# WL-Power.net
KiCad netlist of a schematic drawn in Altium Designer
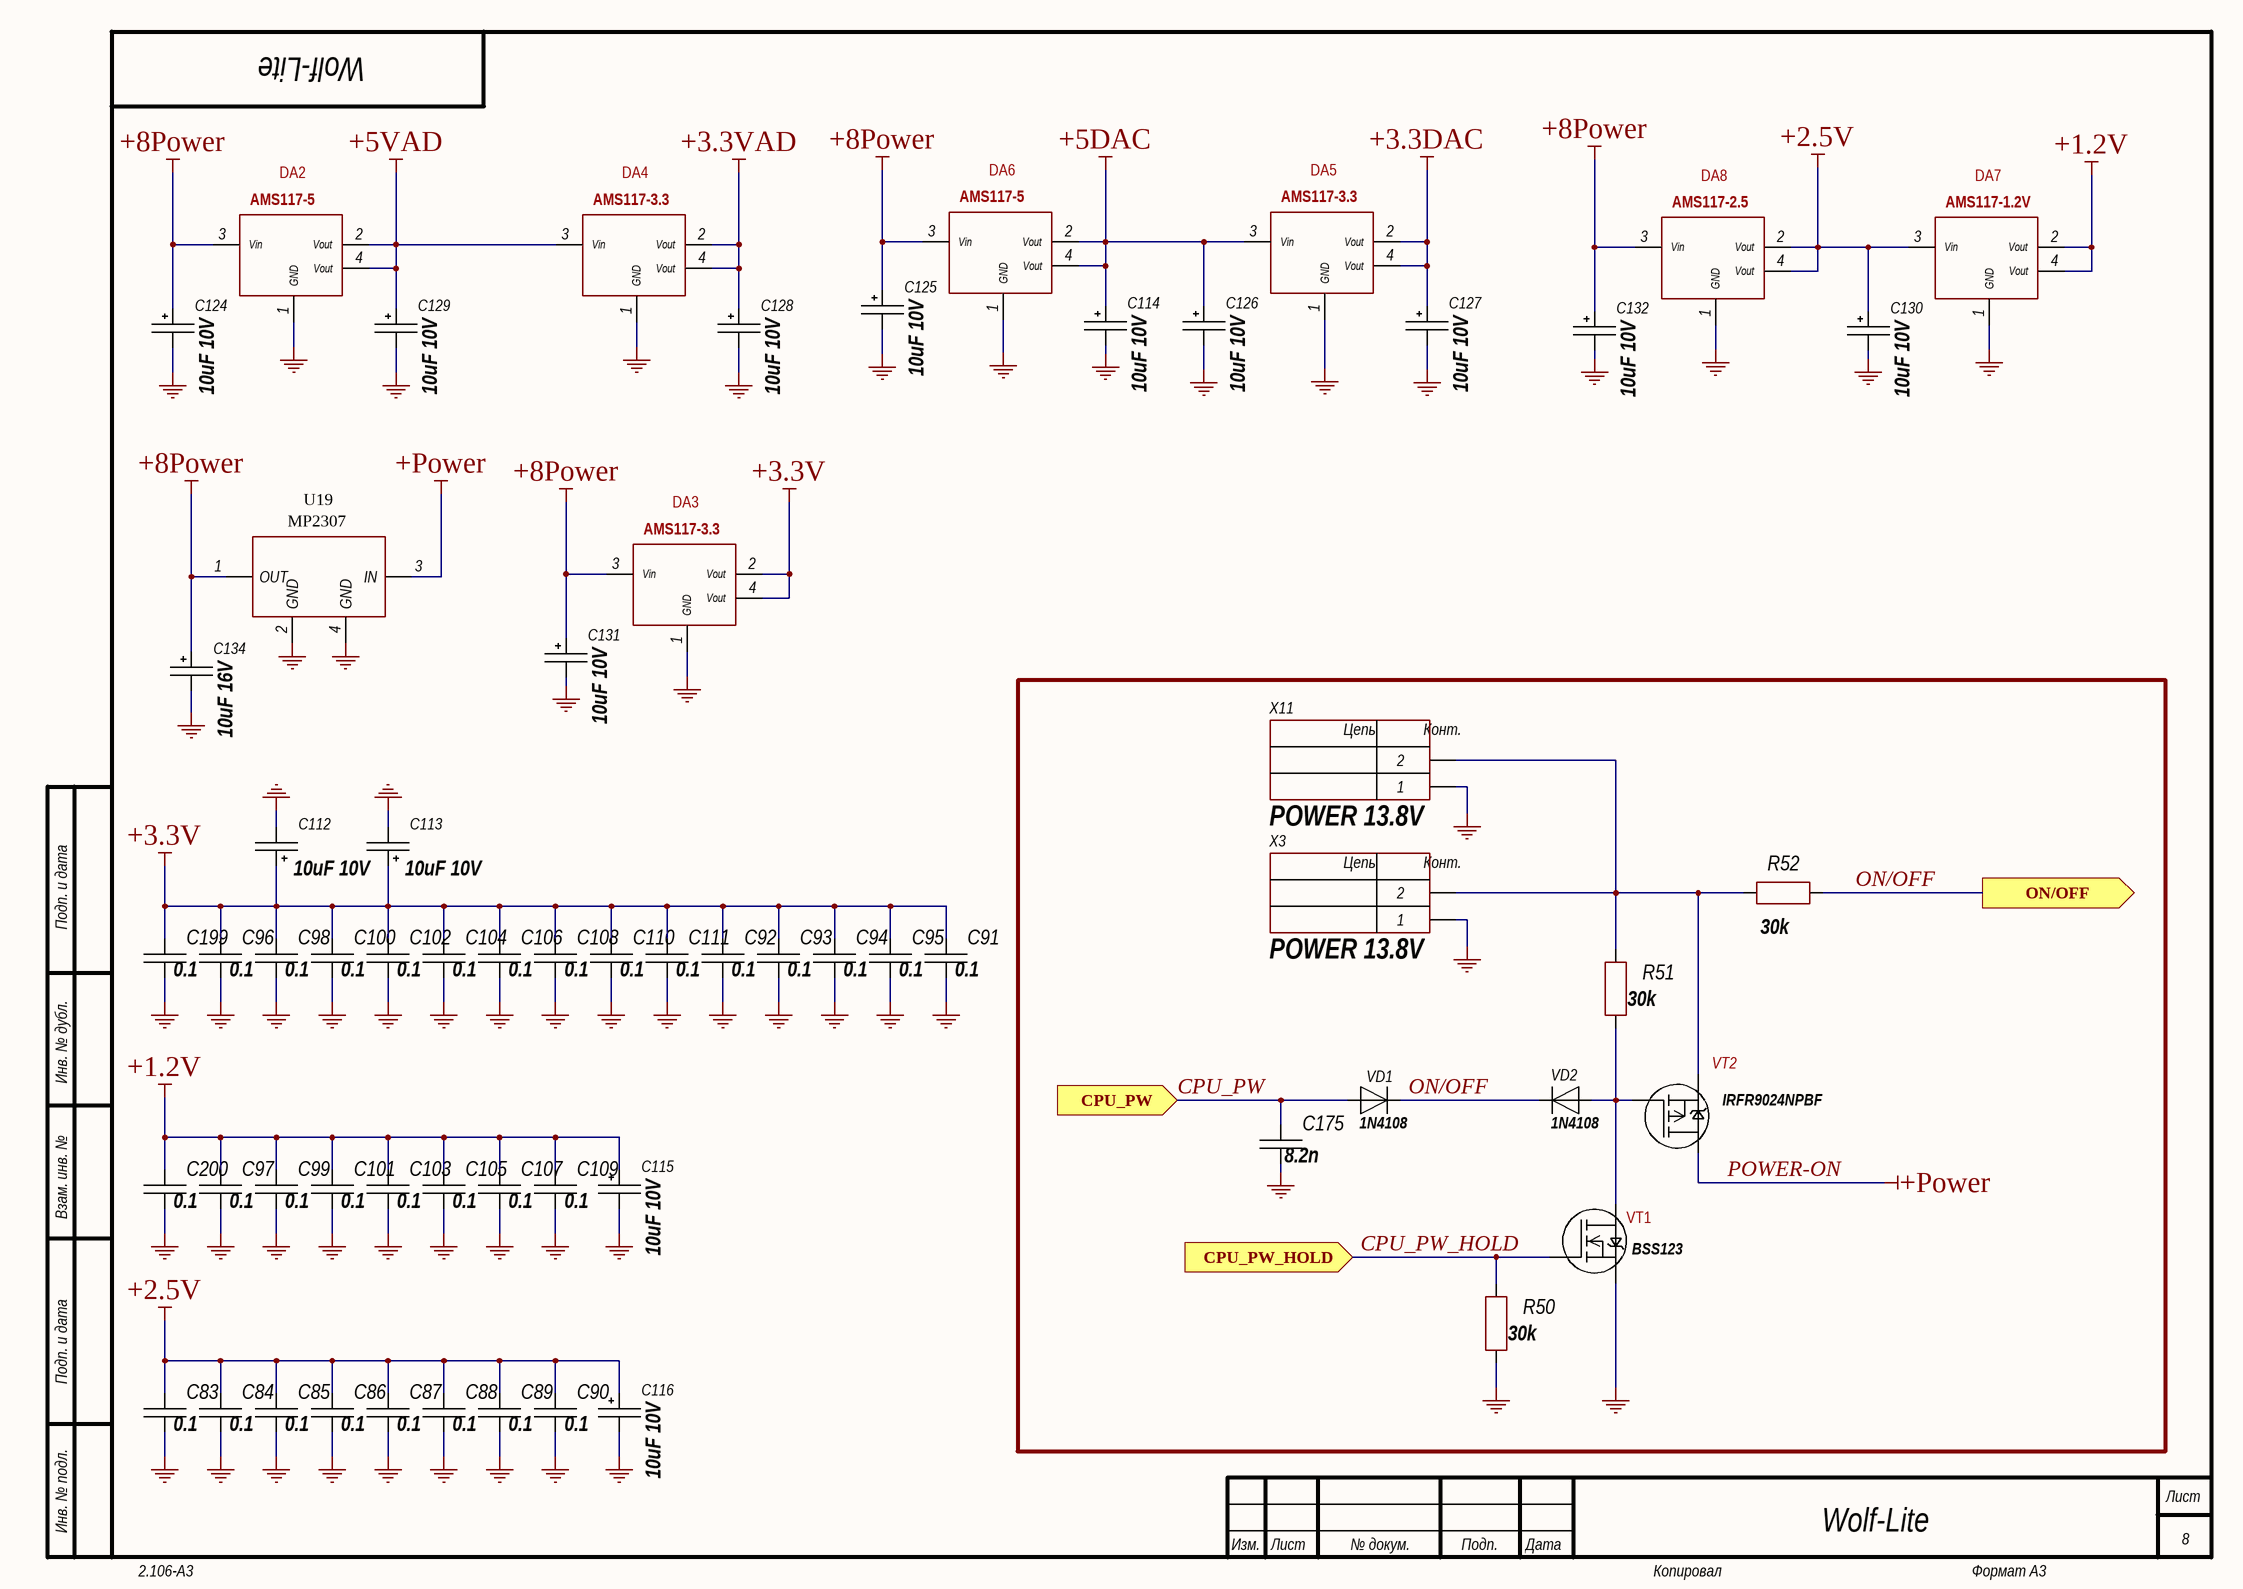
[diagram p0: WL-Power.SchDoc]

(export (version "E")
  (design (tool "Eeschema 10.0.6"))
  (components
    (comp (ref "C83")
      (value "0.1")
      (footprint "standard:CH0805C")
      (libsource (lib "Discrete") (part "Capacitor"))
    )
    (comp (ref "C84")
      (value "0.1")
      (footprint "standard:CH0805C")
      (libsource (lib "Discrete") (part "Capacitor"))
    )
    (comp (ref "C85")
      (value "0.1")
      (footprint "standard:CH0805C")
      (libsource (lib "Discrete") (part "Capacitor"))
    )
    (comp (ref "C86")
      (value "0.1")
      (footprint "standard:CH0805C")
      (libsource (lib "Discrete") (part "Capacitor"))
    )
    (comp (ref "C87")
      (value "0.1")
      (footprint "standard:CH0805C")
      (libsource (lib "Discrete") (part "Capacitor"))
    )
    (comp (ref "C88")
      (value "0.1")
      (footprint "standard:CH0805C")
      (libsource (lib "Discrete") (part "Capacitor"))
    )
    (comp (ref "C89")
      (value "0.1")
      (footprint "standard:CH0805C")
      (libsource (lib "Discrete") (part "Capacitor"))
    )
    (comp (ref "C90")
      (value "0.1")
      (footprint "standard:CH0805C")
      (libsource (lib "Discrete") (part "Capacitor"))
    )
    (comp (ref "C91")
      (value "0.1")
      (footprint "standard:CH0805C")
      (libsource (lib "Discrete") (part "Capacitor"))
    )
    (comp (ref "C92")
      (value "0.1")
      (footprint "standard:CH0805C")
      (libsource (lib "Discrete") (part "Capacitor"))
    )
    (comp (ref "C93")
      (value "0.1")
      (footprint "standard:CH0805C")
      (libsource (lib "Discrete") (part "Capacitor"))
    )
    (comp (ref "C94")
      (value "0.1")
      (footprint "standard:CH0805C")
      (libsource (lib "Discrete") (part "Capacitor"))
    )
    (comp (ref "C95")
      (value "0.1")
      (footprint "standard:CH0805C")
      (libsource (lib "Discrete") (part "Capacitor"))
    )
    (comp (ref "C96")
      (value "0.1")
      (footprint "standard:CH0805C")
      (libsource (lib "Discrete") (part "Capacitor"))
    )
    (comp (ref "C97")
      (value "0.1")
      (footprint "standard:CH0805C")
      (libsource (lib "Discrete") (part "Capacitor"))
    )
    (comp (ref "C98")
      (value "0.1")
      (footprint "standard:CH0805C")
      (libsource (lib "Discrete") (part "Capacitor"))
    )
    (comp (ref "C99")
      (value "0.1")
      (footprint "standard:CH0805C")
      (libsource (lib "Discrete") (part "Capacitor"))
    )
    (comp (ref "C100")
      (value "0.1")
      (footprint "standard:CH0805C")
      (libsource (lib "Discrete") (part "Capacitor"))
    )
    (comp (ref "C101")
      (value "0.1")
      (footprint "standard:CH0805C")
      (libsource (lib "Discrete") (part "Capacitor"))
    )
    (comp (ref "C102")
      (value "0.1")
      (footprint "standard:CH0805C")
      (libsource (lib "Discrete") (part "Capacitor"))
    )
    (comp (ref "C103")
      (value "0.1")
      (footprint "standard:CH0805C")
      (libsource (lib "Discrete") (part "Capacitor"))
    )
    (comp (ref "C104")
      (value "0.1")
      (footprint "standard:CH0805C")
      (libsource (lib "Discrete") (part "Capacitor"))
    )
    (comp (ref "C105")
      (value "0.1")
      (footprint "standard:CH0805C")
      (libsource (lib "Discrete") (part "Capacitor"))
    )
    (comp (ref "C106")
      (value "0.1")
      (footprint "standard:CH0805C")
      (libsource (lib "Discrete") (part "Capacitor"))
    )
    (comp (ref "C107")
      (value "0.1")
      (footprint "standard:CH0805C")
      (libsource (lib "Discrete") (part "Capacitor"))
    )
    (comp (ref "C108")
      (value "0.1")
      (footprint "standard:CH0805C")
      (libsource (lib "Discrete") (part "Capacitor"))
    )
    (comp (ref "C109")
      (value "0.1")
      (footprint "standard:CH0805C")
      (libsource (lib "Discrete") (part "Capacitor"))
    )
    (comp (ref "C110")
      (value "0.1")
      (footprint "standard:CH0805C")
      (libsource (lib "Discrete") (part "Capacitor"))
    )
    (comp (ref "C111")
      (value "0.1")
      (footprint "standard:CH0805C")
      (libsource (lib "Discrete") (part "Capacitor"))
    )
    (comp (ref "C112")
      (value "10uF 10V")
      (footprint "standard:TANTAL_B")
      (libsource (lib "Discrete") (part "TantalCap"))
    )
    (comp (ref "C113")
      (value "10uF 10V")
      (footprint "standard:TANTAL_B")
      (libsource (lib "Discrete") (part "TantalCap"))
    )
    (comp (ref "C114")
      (value "10uF 10V")
      (footprint "standard:TANTAL_B")
      (libsource (lib "Discrete") (part "TantalCap"))
    )
    (comp (ref "C115")
      (value "10uF 10V")
      (footprint "standard:TANTAL_B")
      (libsource (lib "Discrete") (part "TantalCap"))
    )
    (comp (ref "C116")
      (value "10uF 10V")
      (footprint "standard:TANTAL_B")
      (libsource (lib "Discrete") (part "TantalCap"))
    )
    (comp (ref "C124")
      (value "10uF 10V")
      (footprint "standard:TANTAL_B")
      (libsource (lib "Discrete") (part "TantalCap"))
    )
    (comp (ref "C125")
      (value "10uF 10V")
      (footprint "standard:TANTAL_B")
      (libsource (lib "Discrete") (part "TantalCap"))
    )
    (comp (ref "C126")
      (value "10uF 10V")
      (footprint "standard:TANTAL_B")
      (libsource (lib "Discrete") (part "TantalCap"))
    )
    (comp (ref "C127")
      (value "10uF 10V")
      (footprint "standard:TANTAL_B")
      (libsource (lib "Discrete") (part "TantalCap"))
    )
    (comp (ref "C128")
      (value "10uF 10V")
      (footprint "standard:TANTAL_B")
      (libsource (lib "Discrete") (part "TantalCap"))
    )
    (comp (ref "C129")
      (value "10uF 10V")
      (footprint "standard:TANTAL_B")
      (libsource (lib "Discrete") (part "TantalCap"))
    )
    (comp (ref "C130")
      (value "10uF 10V")
      (footprint "standard:TANTAL_B")
      (libsource (lib "Discrete") (part "TantalCap"))
    )
    (comp (ref "C131")
      (value "10uF 10V")
      (footprint "standard:TANTAL_B")
      (libsource (lib "Discrete") (part "TantalCap"))
    )
    (comp (ref "C132")
      (value "10uF 10V")
      (footprint "standard:TANTAL_B")
      (libsource (lib "Discrete") (part "TantalCap"))
    )
    (comp (ref "C134")
      (value "10uF 16V")
      (footprint "POLIMER-D")
      (libsource (lib "Discrete") (part "TantalCap"))
    )
    (comp (ref "C175")
      (value "8.2n")
      (footprint "standard:CH0805C")
      (libsource (lib "Discrete") (part "Capacitor"))
    )
    (comp (ref "C199")
      (value "0.1")
      (footprint "standard:CH0805C")
      (libsource (lib "Discrete") (part "Capacitor"))
    )
    (comp (ref "C200")
      (value "0.1")
      (footprint "standard:CH0805C")
      (libsource (lib "Discrete") (part "Capacitor"))
    )
    (comp (ref "DA2") (value "AMS117-5") (footprint "SOT223") (libsource (lib "Analog") (part "AMS117")))
    (comp (ref "DA3") (value "AMS117-3.3") (footprint "SOT223") (libsource (lib "Analog") (part "AMS117")))
    (comp (ref "DA4") (value "AMS117-3.3") (footprint "SOT223") (libsource (lib "Analog") (part "AMS117")))
    (comp (ref "DA5") (value "AMS117-3.3") (footprint "SOT223") (libsource (lib "Analog") (part "AMS117")))
    (comp (ref "DA6") (value "AMS117-5") (footprint "SOT223") (libsource (lib "Analog") (part "AMS117")))
    (comp (ref "DA7") (value "AMS117-1.2V") (footprint "SOT223") (libsource (lib "Analog") (part "AMS117")))
    (comp (ref "DA8") (value "AMS117-2.5") (footprint "SOT223") (libsource (lib "Analog") (part "AMS117")))
    (comp (ref "R50")
      (value "30k")
      (footprint "standard:CH0805R")
      (libsource (lib "Discrete") (part "Resistor"))
    )
    (comp (ref "R51")
      (value "30k")
      (footprint "standard:CH0805R")
      (libsource (lib "Discrete") (part "Resistor"))
    )
    (comp (ref "R52") (value "30k") (footprint "standard:CH0805R") (libsource (lib "") (part "Resistor_1")))
    (comp (ref "U19")
      (value "MP2307")
      (footprint "MP2307 MINI360")
      (libsource (lib "Power Supplies") (part "MP2307"))
    )
    (comp (ref "VD1") (value "1N4108") (footprint "1N4148") (libsource (lib "Diods") (part "Diod")))
    (comp (ref "VD2") (value "1N4108") (footprint "1N4148") (libsource (lib "Diods") (part "Diod")))
    (comp (ref "VT1")
      (value "BSS123")
      (footprint "SOT23_132")
      (libsource (lib "Transistor") (part "N-KANAL"))
    )
    (comp (ref "VT2")
      (value "IRFR9024NPBF")
      (footprint "D2PAK_132")
      (libsource (lib "Transistor") (part "P-KANAL"))
    )
    (comp (ref "X3")
      (value "POWER 13.8V")
      (footprint "custom:CON: 300-02P-5.0")
      (libsource (lib "Connectors") (part "2-Connector"))
    )
    (comp (ref "X11")
      (value "POWER 13.8V")
      (footprint "custom:CON: 300-02P-5.0")
      (libsource (lib "Connectors") (part "2-Connector"))
    )
  )
  (nets
    (net (code "1") (name "+1.2V") (class "Default")
      (node (ref "C101") (pin "1") (pinfunction "1_1") (pintype "power_in"))
      (node (ref "C103") (pin "1") (pinfunction "1_1") (pintype "power_in"))
      (node (ref "C105") (pin "1") (pinfunction "1_1") (pintype "power_in"))
      (node (ref "C107") (pin "1") (pinfunction "1_1") (pintype "power_in"))
      (node (ref "C109") (pin "1") (pinfunction "1_1") (pintype "power_in"))
      (node (ref "C115") (pin "1") (pinfunction "1_1") (pintype "power_in"))
      (node (ref "C200") (pin "1") (pinfunction "1_1") (pintype "power_in"))
      (node (ref "C97") (pin "1") (pinfunction "1_1") (pintype "power_in"))
      (node (ref "C99") (pin "1") (pinfunction "1_1") (pintype "power_in"))
      (node (ref "DA7") (pin "2") (pinfunction "Vout_2") (pintype "passive"))
      (node (ref "DA7") (pin "4") (pinfunction "Vout_4") (pintype "passive"))
    )
    (net (code "2") (name "+2.5V") (class "Default")
      (node (ref "C116") (pin "1") (pinfunction "1_1") (pintype "power_in"))
      (node (ref "C130") (pin "1") (pinfunction "1_1") (pintype "power_in"))
      (node (ref "C83") (pin "1") (pinfunction "1_1") (pintype "power_in"))
      (node (ref "C84") (pin "1") (pinfunction "1_1") (pintype "power_in"))
      (node (ref "C85") (pin "1") (pinfunction "1_1") (pintype "power_in"))
      (node (ref "C86") (pin "1") (pinfunction "1_1") (pintype "power_in"))
      (node (ref "C87") (pin "1") (pinfunction "1_1") (pintype "power_in"))
      (node (ref "C88") (pin "1") (pinfunction "1_1") (pintype "power_in"))
      (node (ref "C89") (pin "1") (pinfunction "1_1") (pintype "power_in"))
      (node (ref "C90") (pin "1") (pinfunction "1_1") (pintype "power_in"))
      (node (ref "DA7") (pin "3") (pinfunction "Vin_3") (pintype "passive"))
      (node (ref "DA8") (pin "2") (pinfunction "Vout_2") (pintype "passive"))
      (node (ref "DA8") (pin "4") (pinfunction "Vout_4") (pintype "passive"))
    )
    (net (code "3") (name "+3.3DAC") (class "Default")
      (node (ref "C127") (pin "1") (pinfunction "1_1") (pintype "power_in"))
      (node (ref "DA5") (pin "2") (pinfunction "Vout_2") (pintype "passive"))
      (node (ref "DA5") (pin "4") (pinfunction "Vout_4") (pintype "passive"))
    )
    (net (code "4") (name "+3.3V") (class "Default")
      (node (ref "C100") (pin "1") (pinfunction "1_1") (pintype "power_in"))
      (node (ref "C102") (pin "1") (pinfunction "1_1") (pintype "power_in"))
      (node (ref "C104") (pin "1") (pinfunction "1_1") (pintype "power_in"))
      (node (ref "C106") (pin "1") (pinfunction "1_1") (pintype "power_in"))
      (node (ref "C108") (pin "1") (pinfunction "1_1") (pintype "power_in"))
      (node (ref "C110") (pin "1") (pinfunction "1_1") (pintype "power_in"))
      (node (ref "C111") (pin "1") (pinfunction "1_1") (pintype "power_in"))
      (node (ref "C112") (pin "1") (pinfunction "1_1") (pintype "power_in"))
      (node (ref "C113") (pin "1") (pinfunction "1_1") (pintype "power_in"))
      (node (ref "C199") (pin "1") (pinfunction "1_1") (pintype "power_in"))
      (node (ref "C91") (pin "1") (pinfunction "1_1") (pintype "power_in"))
      (node (ref "C92") (pin "1") (pinfunction "1_1") (pintype "power_in"))
      (node (ref "C93") (pin "1") (pinfunction "1_1") (pintype "power_in"))
      (node (ref "C94") (pin "1") (pinfunction "1_1") (pintype "power_in"))
      (node (ref "C95") (pin "1") (pinfunction "1_1") (pintype "power_in"))
      (node (ref "C96") (pin "1") (pinfunction "1_1") (pintype "power_in"))
      (node (ref "C98") (pin "1") (pinfunction "1_1") (pintype "power_in"))
      (node (ref "DA3") (pin "2") (pinfunction "Vout_2") (pintype "passive"))
      (node (ref "DA3") (pin "4") (pinfunction "Vout_4") (pintype "passive"))
    )
    (net (code "5") (name "+3.3VAD") (class "Default")
      (node (ref "C128") (pin "1") (pinfunction "1_1") (pintype "power_in"))
      (node (ref "DA4") (pin "2") (pinfunction "Vout_2") (pintype "passive"))
      (node (ref "DA4") (pin "4") (pinfunction "Vout_4") (pintype "passive"))
    )
    (net (code "6") (name "+5DAC") (class "Default")
      (node (ref "C114") (pin "1") (pinfunction "1_1") (pintype "power_in"))
      (node (ref "C126") (pin "1") (pinfunction "1_1") (pintype "power_in"))
      (node (ref "DA5") (pin "3") (pinfunction "Vin_3") (pintype "passive"))
      (node (ref "DA6") (pin "2") (pinfunction "Vout_2") (pintype "passive"))
      (node (ref "DA6") (pin "4") (pinfunction "Vout_4") (pintype "passive"))
    )
    (net (code "7") (name "+5VAD") (class "Default")
      (node (ref "C129") (pin "1") (pinfunction "1_1") (pintype "power_in"))
      (node (ref "DA2") (pin "2") (pinfunction "Vout_2") (pintype "passive"))
      (node (ref "DA2") (pin "4") (pinfunction "Vout_4") (pintype "passive"))
      (node (ref "DA4") (pin "3") (pinfunction "Vin_3") (pintype "passive"))
    )
    (net (code "8") (name "+8Power") (class "Default")
      (node (ref "C124") (pin "1") (pinfunction "1_1") (pintype "power_in"))
      (node (ref "C125") (pin "1") (pinfunction "1_1") (pintype "power_in"))
      (node (ref "C131") (pin "1") (pinfunction "1_1") (pintype "power_in"))
      (node (ref "C132") (pin "1") (pinfunction "1_1") (pintype "power_in"))
      (node (ref "C134") (pin "1") (pinfunction "1_1") (pintype "power_in"))
      (node (ref "DA2") (pin "3") (pinfunction "Vin_3") (pintype "passive"))
      (node (ref "DA3") (pin "3") (pinfunction "Vin_3") (pintype "passive"))
      (node (ref "DA6") (pin "3") (pinfunction "Vin_3") (pintype "passive"))
      (node (ref "DA8") (pin "3") (pinfunction "Vin_3") (pintype "passive"))
      (node (ref "U19") (pin "1") (pinfunction "OUT_1") (pintype "power_in"))
    )
    (net (code "9") (name "+Power") (class "Default")
      (node (ref "U19") (pin "3") (pinfunction "IN_3") (pintype "passive"))
      (node (ref "VT2") (pin "3") (pinfunction "D_3") (pintype "passive"))
    )
    (net (code "10") (name "/CPU_PW") (class "Default")
      (node (ref "C175") (pin "1") (pinfunction "1_1") (pintype "power_in"))
      (node (ref "VD1") (pin "1") (pinfunction "1_1") (pintype "passive"))
    )
    (net (code "11") (name "/CPU_PW_HOLD") (class "Default")
      (node (ref "R50") (pin "2") (pinfunction "2_2") (pintype "passive"))
      (node (ref "VT1") (pin "1") (pinfunction "Затвор(Gate)_1") (pintype "passive"))
    )
    (net (code "12") (name "/ON{slash}OFF") (class "Default")
      (node (ref "R52") (pin "1") (pinfunction "1_1") (pintype "passive"))
      (node (ref "VD1") (pin "2") (pinfunction "2_2") (pintype "passive"))
      (node (ref "VD2") (pin "2") (pinfunction "2_2") (pintype "passive"))
    )
    (net (code "13") (name "GND") (class "Default")
      (node (ref "C100") (pin "2") (pinfunction "2_2") (pintype "power_in"))
      (node (ref "C101") (pin "2") (pinfunction "2_2") (pintype "power_in"))
      (node (ref "C102") (pin "2") (pinfunction "2_2") (pintype "power_in"))
      (node (ref "C103") (pin "2") (pinfunction "2_2") (pintype "power_in"))
      (node (ref "C104") (pin "2") (pinfunction "2_2") (pintype "power_in"))
      (node (ref "C105") (pin "2") (pinfunction "2_2") (pintype "power_in"))
      (node (ref "C106") (pin "2") (pinfunction "2_2") (pintype "power_in"))
      (node (ref "C107") (pin "2") (pinfunction "2_2") (pintype "power_in"))
      (node (ref "C108") (pin "2") (pinfunction "2_2") (pintype "power_in"))
      (node (ref "C109") (pin "2") (pinfunction "2_2") (pintype "power_in"))
      (node (ref "C110") (pin "2") (pinfunction "2_2") (pintype "power_in"))
      (node (ref "C111") (pin "2") (pinfunction "2_2") (pintype "power_in"))
      (node (ref "C112") (pin "2") (pinfunction "2_2") (pintype "power_in"))
      (node (ref "C113") (pin "2") (pinfunction "2_2") (pintype "power_in"))
      (node (ref "C114") (pin "2") (pinfunction "2_2") (pintype "power_in"))
      (node (ref "C115") (pin "2") (pinfunction "2_2") (pintype "power_in"))
      (node (ref "C116") (pin "2") (pinfunction "2_2") (pintype "power_in"))
      (node (ref "C124") (pin "2") (pinfunction "2_2") (pintype "power_in"))
      (node (ref "C125") (pin "2") (pinfunction "2_2") (pintype "power_in"))
      (node (ref "C126") (pin "2") (pinfunction "2_2") (pintype "power_in"))
      (node (ref "C127") (pin "2") (pinfunction "2_2") (pintype "power_in"))
      (node (ref "C128") (pin "2") (pinfunction "2_2") (pintype "power_in"))
      (node (ref "C129") (pin "2") (pinfunction "2_2") (pintype "power_in"))
      (node (ref "C130") (pin "2") (pinfunction "2_2") (pintype "power_in"))
      (node (ref "C131") (pin "2") (pinfunction "2_2") (pintype "power_in"))
      (node (ref "C132") (pin "2") (pinfunction "2_2") (pintype "power_in"))
      (node (ref "C134") (pin "2") (pinfunction "2_2") (pintype "power_in"))
      (node (ref "C175") (pin "2") (pinfunction "2_2") (pintype "power_in"))
      (node (ref "C199") (pin "2") (pinfunction "2_2") (pintype "power_in"))
      (node (ref "C200") (pin "2") (pinfunction "2_2") (pintype "power_in"))
      (node (ref "C83") (pin "2") (pinfunction "2_2") (pintype "power_in"))
      (node (ref "C84") (pin "2") (pinfunction "2_2") (pintype "power_in"))
      (node (ref "C85") (pin "2") (pinfunction "2_2") (pintype "power_in"))
      (node (ref "C86") (pin "2") (pinfunction "2_2") (pintype "power_in"))
      (node (ref "C87") (pin "2") (pinfunction "2_2") (pintype "power_in"))
      (node (ref "C88") (pin "2") (pinfunction "2_2") (pintype "power_in"))
      (node (ref "C89") (pin "2") (pinfunction "2_2") (pintype "power_in"))
      (node (ref "C90") (pin "2") (pinfunction "2_2") (pintype "power_in"))
      (node (ref "C91") (pin "2") (pinfunction "2_2") (pintype "power_in"))
      (node (ref "C92") (pin "2") (pinfunction "2_2") (pintype "power_in"))
      (node (ref "C93") (pin "2") (pinfunction "2_2") (pintype "power_in"))
      (node (ref "C94") (pin "2") (pinfunction "2_2") (pintype "power_in"))
      (node (ref "C95") (pin "2") (pinfunction "2_2") (pintype "power_in"))
      (node (ref "C96") (pin "2") (pinfunction "2_2") (pintype "power_in"))
      (node (ref "C97") (pin "2") (pinfunction "2_2") (pintype "power_in"))
      (node (ref "C98") (pin "2") (pinfunction "2_2") (pintype "power_in"))
      (node (ref "C99") (pin "2") (pinfunction "2_2") (pintype "power_in"))
      (node (ref "DA2") (pin "1") (pinfunction "GND_1") (pintype "passive"))
      (node (ref "DA3") (pin "1") (pinfunction "GND_1") (pintype "passive"))
      (node (ref "DA4") (pin "1") (pinfunction "GND_1") (pintype "passive"))
      (node (ref "DA5") (pin "1") (pinfunction "GND_1") (pintype "passive"))
      (node (ref "DA6") (pin "1") (pinfunction "GND_1") (pintype "passive"))
      (node (ref "DA7") (pin "1") (pinfunction "GND_1") (pintype "passive"))
      (node (ref "DA8") (pin "1") (pinfunction "GND_1") (pintype "passive"))
      (node (ref "R50") (pin "1") (pinfunction "1_1") (pintype "passive"))
      (node (ref "U19") (pin "2") (pinfunction "GND_2") (pintype "passive"))
      (node (ref "U19") (pin "4") (pinfunction "GND_4") (pintype "passive"))
      (node (ref "VT1") (pin "2") (pinfunction "I_2") (pintype "passive"))
      (node (ref "X11") (pin "1") (pinfunction "1_1") (pintype "passive"))
      (node (ref "X3") (pin "1") (pinfunction "1_1") (pintype "passive"))
    )
    (net (code "14") (name "Net-(VT1-Сток(Drain))") (class "Default")
      (node (ref "R51") (pin "1") (pinfunction "1_1") (pintype "passive"))
      (node (ref "VD2") (pin "1") (pinfunction "1_1") (pintype "passive"))
      (node (ref "VT1") (pin "3") (pinfunction "Сток(Drain)_3") (pintype "passive"))
      (node (ref "VT2") (pin "1") (pinfunction "Затвор(Gate)_1") (pintype "passive"))
    )
    (net (code "15") (name "Net-(VT2-S)") (class "Default")
      (node (ref "R51") (pin "2") (pinfunction "2_2") (pintype "passive"))
      (node (ref "R52") (pin "2") (pinfunction "2_2") (pintype "passive"))
      (node (ref "VT2") (pin "2") (pinfunction "S_2") (pintype "passive"))
      (node (ref "X11") (pin "2") (pinfunction "2_2") (pintype "passive"))
      (node (ref "X3") (pin "2") (pinfunction "2_2") (pintype "passive"))
    )
  )
)
